# 8052.net
KiCad netlist of a schematic drawn in EAGLE
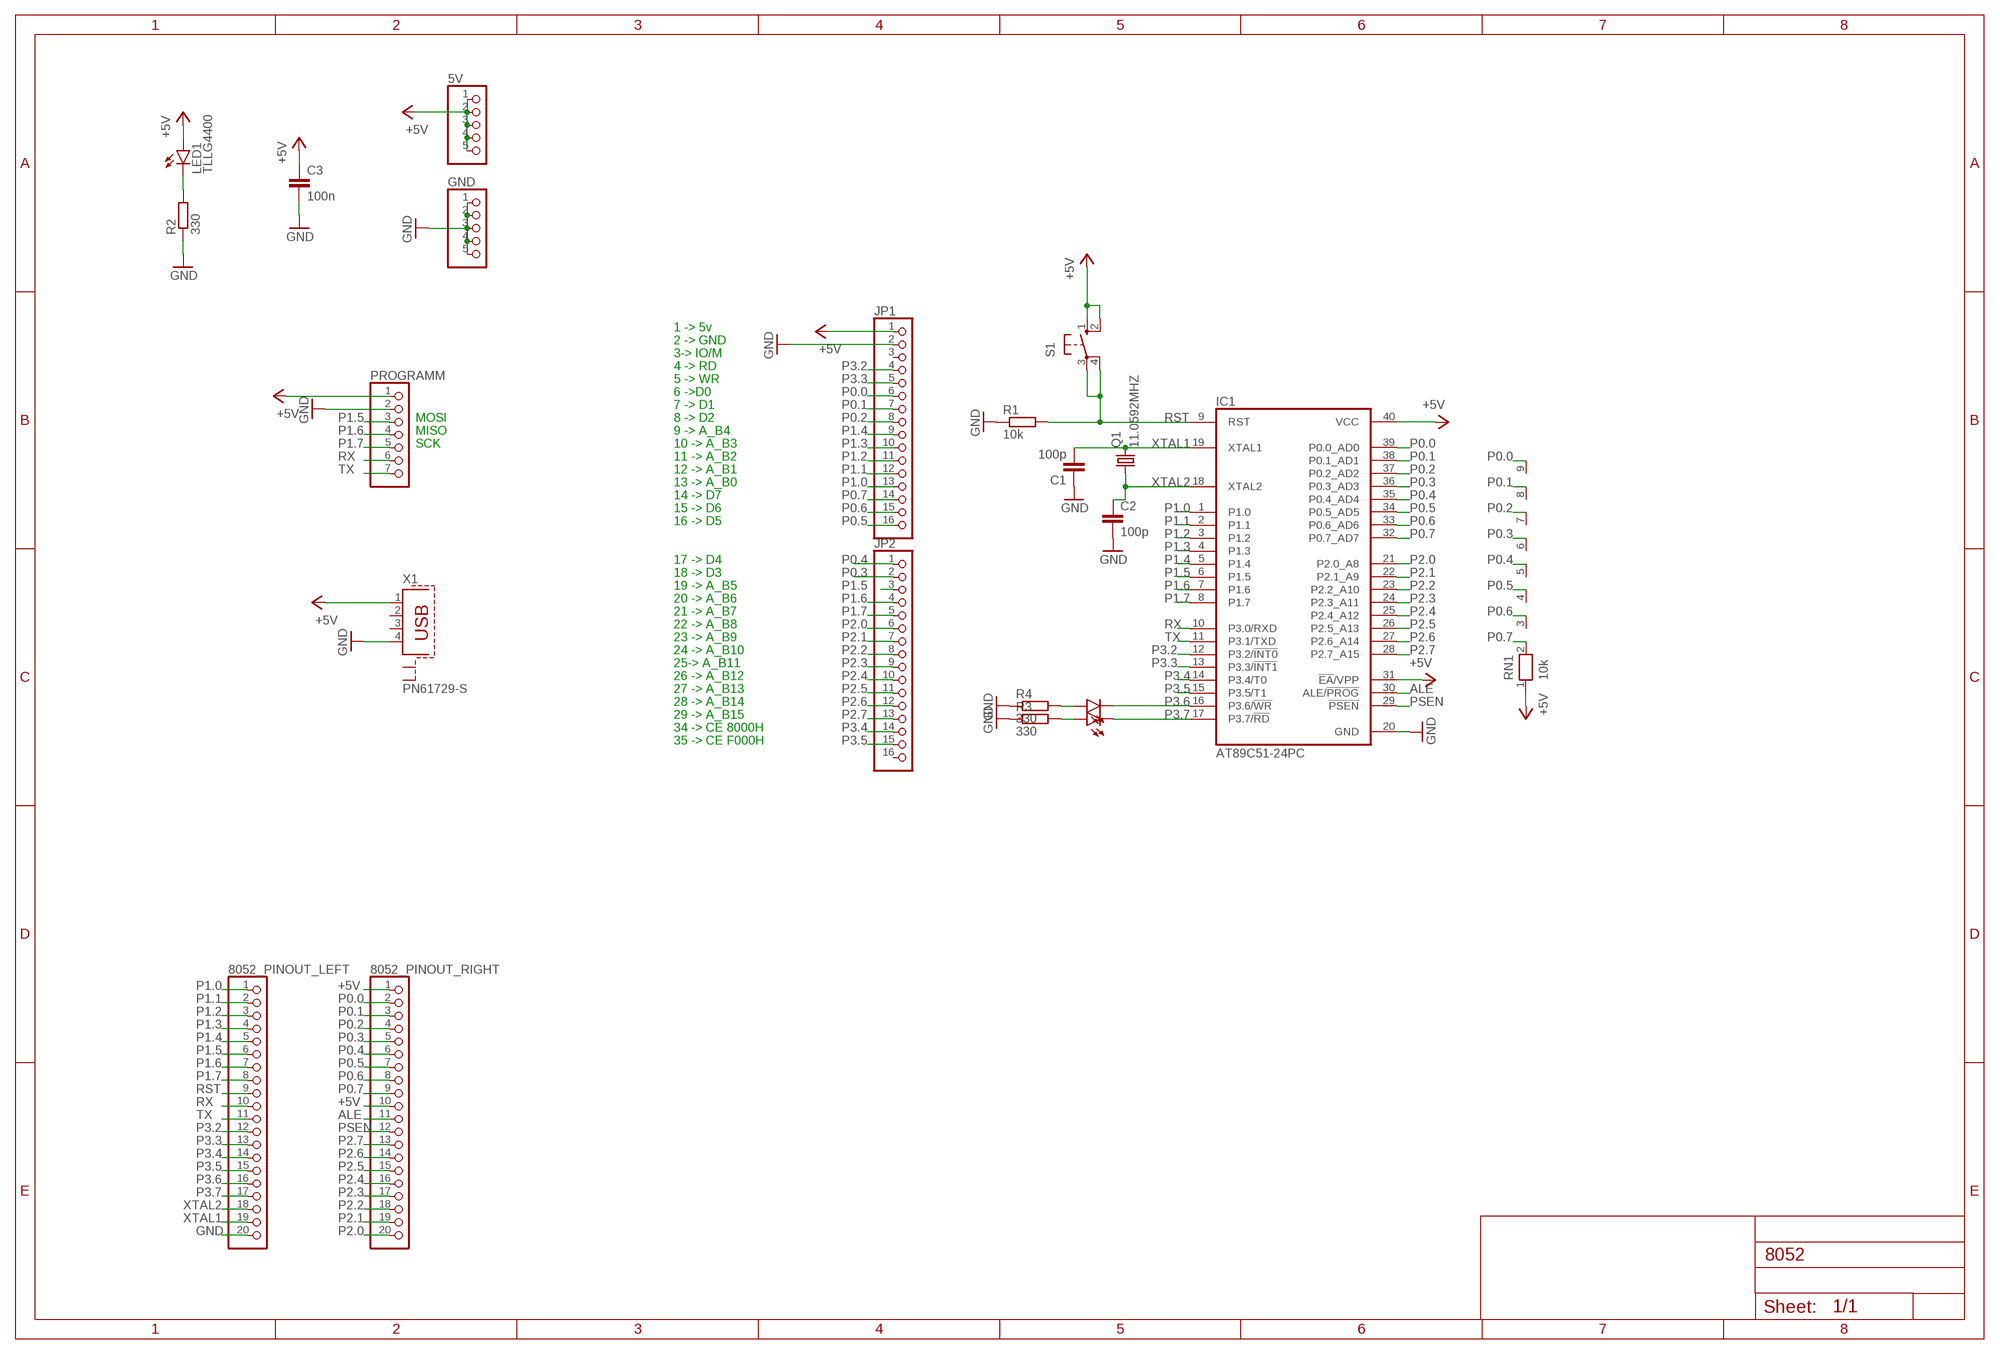
[diagram p0: schematic, sheet 1]

(export (version "E")
  (design (tool "Eeschema 10.0.6"))
  (components
    (comp (ref "5V")
      (value "PINHD-1X5")
      (footprint "eagle-import:1X05")
      (libsource (lib "eagle-import") (part "PINHD-1X5"))
    )
    (comp (ref "8052_PINOUT_LEFT")
      (value "PINHD-1X20")
      (footprint "eagle-import:1X20")
      (libsource (lib "eagle-import") (part "PINHD-1X20"))
    )
    (comp (ref "8052_PINOUT_RIGHT")
      (value "PINHD-1X20")
      (footprint "eagle-import:1X20")
      (libsource (lib "eagle-import") (part "PINHD-1X20"))
    )
    (comp (ref "C1")
      (value "100p")
      (footprint "eagle-import:C025-024X044")
      (libsource (lib "eagle-import") (part "C-EU025-024X044"))
    )
    (comp (ref "C2")
      (value "100p")
      (footprint "eagle-import:C025-024X044")
      (libsource (lib "eagle-import") (part "C-EU025-024X044"))
    )
    (comp (ref "C3")
      (value "100n")
      (footprint "eagle-import:C025-025X050")
      (libsource (lib "eagle-import") (part "C-EU025-025X050"))
    )
    (comp (ref "GND")
      (value "PINHD-1X5")
      (footprint "eagle-import:1X05")
      (libsource (lib "eagle-import") (part "PINHD-1X5"))
    )
    (comp (ref "IC1")
      (value "AT89C51-24PC")
      (footprint "eagle-import:DIL40")
      (libsource (lib "eagle-import") (part "AT89C51-PC24"))
    )
    (comp (ref "JP1")
      (value "PINHD-1X16")
      (footprint "eagle-import:1X16")
      (libsource (lib "eagle-import") (part "PINHD-1X16"))
    )
    (comp (ref "JP2")
      (value "PINHD-1X16")
      (footprint "eagle-import:1X16")
      (libsource (lib "eagle-import") (part "PINHD-1X16"))
    )
    (comp (ref "LED1")
      (value "TLLG4400")
      (footprint "eagle-import:LED3MM")
      (fields (field (name "MF") "VISHAY SEMICONDUCTOR"))
      (libsource (lib "eagle-import") (part "TLLG4400"))
    )
    (comp (ref "LED2")
      (value "TLLG4400")
      (footprint "eagle-import:LED3MM")
      (fields (field (name "MF") "VISHAY SEMICONDUCTOR"))
      (libsource (lib "eagle-import") (part "TLLG4400"))
    )
    (comp (ref "LED3")
      (value "TLLG4400")
      (footprint "eagle-import:LED3MM")
      (fields (field (name "MF") "VISHAY SEMICONDUCTOR"))
      (libsource (lib "eagle-import") (part "TLLG4400"))
    )
    (comp (ref "PROGRAMM")
      (value "PINHD-1X7/90")
      (footprint "eagle-import:1X07_90")
      (libsource (lib "eagle-import") (part "PINHD-1X7/90"))
    )
    (comp (ref "Q1")
      (value "11.0592MHZ")
      (footprint "eagle-import:HC49_S")
      (libsource (lib "eagle-import") (part "CRYSTALHC49S"))
    )
    (comp (ref "R1")
      (value "10k")
      (footprint "eagle-import:0207_7")
      (libsource (lib "eagle-import") (part "R-EU_0207/7"))
    )
    (comp (ref "R2")
      (value "330")
      (footprint "eagle-import:0207_7")
      (libsource (lib "eagle-import") (part "R-EU_0207/7"))
    )
    (comp (ref "R3")
      (value "330")
      (footprint "eagle-import:0207_7")
      (libsource (lib "eagle-import") (part "R-EU_0207/7"))
    )
    (comp (ref "R4")
      (value "330")
      (footprint "eagle-import:0207_7")
      (libsource (lib "eagle-import") (part "R-EU_0207/7"))
    )
    (comp (ref "RN1")
      (value "10k")
      (footprint "eagle-import:RN-9")
      (libsource (lib "eagle-import") (part "RN08"))
    )
    (comp (ref "S1")
      (value "10-XX")
      (footprint "eagle-import:B3F-10XX")
      (fields (field (name "MPN") "B3F-1000"))
      (libsource (lib "eagle-import") (part "10-XX"))
    )
    (comp (ref "X1")
      (value "PN61729-S")
      (footprint "eagle-import:PN61729-S")
      (libsource (lib "eagle-import") (part "PN61729-S"))
    )
  )
  (nets
    (net (code "1") (name "+5V") (class "Default")
      (node (ref "5V") (pin "1") (pinfunction "1_1") (pintype "passive"))
      (node (ref "5V") (pin "2") (pinfunction "2_2") (pintype "passive"))
      (node (ref "5V") (pin "3") (pinfunction "3_3") (pintype "passive"))
      (node (ref "5V") (pin "4") (pinfunction "4_4") (pintype "passive"))
      (node (ref "5V") (pin "5") (pinfunction "5_5") (pintype "passive"))
      (node (ref "8052_PINOUT_RIGHT") (pin "1") (pinfunction "1_1") (pintype "passive"))
      (node (ref "8052_PINOUT_RIGHT") (pin "10") (pinfunction "10_10") (pintype "passive"))
      (node (ref "C3") (pin "1") (pinfunction "1_1") (pintype "passive"))
      (node (ref "IC1") (pin "31") (pinfunction "~{EA}/VPP_31") (pintype "input"))
      (node (ref "IC1") (pin "40") (pinfunction "VCC_40") (pintype "power_in"))
      (node (ref "JP1") (pin "1") (pinfunction "1_1") (pintype "passive"))
      (node (ref "LED1") (pin "A") (pinfunction "A_A") (pintype "passive"))
      (node (ref "PROGRAMM") (pin "1") (pinfunction "1_1") (pintype "passive"))
      (node (ref "RN1") (pin "1") (pinfunction "1_1") (pintype "passive"))
      (node (ref "S1") (pin "1") (pinfunction "S_1") (pintype "passive"))
      (node (ref "S1") (pin "2") (pinfunction "S1_2") (pintype "passive"))
      (node (ref "X1") (pin "1") (pinfunction "1_1") (pintype "passive"))
    )
    (net (code "2") (name "/ALE") (class "Default")
      (node (ref "8052_PINOUT_RIGHT") (pin "11") (pinfunction "11_11") (pintype "passive"))
      (node (ref "IC1") (pin "30") (pinfunction "ALE/~{PROG}_30") (pintype "output"))
    )
    (net (code "3") (name "/P0.0") (class "Default")
      (node (ref "8052_PINOUT_RIGHT") (pin "2") (pinfunction "2_2") (pintype "passive"))
      (node (ref "IC1") (pin "39") (pinfunction "P0.0_AD0_39") (pintype "bidirectional"))
      (node (ref "JP1") (pin "6") (pinfunction "6_6") (pintype "passive"))
      (node (ref "RN1") (pin "9") (pinfunction "9_9") (pintype "passive"))
    )
    (net (code "4") (name "/P0.1") (class "Default")
      (node (ref "8052_PINOUT_RIGHT") (pin "3") (pinfunction "3_3") (pintype "passive"))
      (node (ref "IC1") (pin "38") (pinfunction "P0.1_AD1_38") (pintype "bidirectional"))
      (node (ref "JP1") (pin "7") (pinfunction "7_7") (pintype "passive"))
      (node (ref "RN1") (pin "8") (pinfunction "8_8") (pintype "passive"))
    )
    (net (code "5") (name "/P0.2") (class "Default")
      (node (ref "8052_PINOUT_RIGHT") (pin "4") (pinfunction "4_4") (pintype "passive"))
      (node (ref "IC1") (pin "37") (pinfunction "P0.2_AD2_37") (pintype "bidirectional"))
      (node (ref "JP1") (pin "8") (pinfunction "8_8") (pintype "passive"))
      (node (ref "RN1") (pin "7") (pinfunction "7_7") (pintype "passive"))
    )
    (net (code "6") (name "/P0.3") (class "Default")
      (node (ref "8052_PINOUT_RIGHT") (pin "5") (pinfunction "5_5") (pintype "passive"))
      (node (ref "IC1") (pin "36") (pinfunction "P0.3_AD3_36") (pintype "bidirectional"))
      (node (ref "JP2") (pin "2") (pinfunction "2_2") (pintype "passive"))
      (node (ref "RN1") (pin "6") (pinfunction "6_6") (pintype "passive"))
    )
    (net (code "7") (name "/P0.4") (class "Default")
      (node (ref "8052_PINOUT_RIGHT") (pin "6") (pinfunction "6_6") (pintype "passive"))
      (node (ref "IC1") (pin "35") (pinfunction "P0.4_AD4_35") (pintype "bidirectional"))
      (node (ref "JP2") (pin "1") (pinfunction "1_1") (pintype "passive"))
      (node (ref "RN1") (pin "5") (pinfunction "5_5") (pintype "passive"))
    )
    (net (code "8") (name "/P0.5") (class "Default")
      (node (ref "8052_PINOUT_RIGHT") (pin "7") (pinfunction "7_7") (pintype "passive"))
      (node (ref "IC1") (pin "34") (pinfunction "P0.5_AD5_34") (pintype "bidirectional"))
      (node (ref "JP1") (pin "16") (pinfunction "16_16") (pintype "passive"))
      (node (ref "RN1") (pin "4") (pinfunction "4_4") (pintype "passive"))
    )
    (net (code "9") (name "/P0.6") (class "Default")
      (node (ref "8052_PINOUT_RIGHT") (pin "8") (pinfunction "8_8") (pintype "passive"))
      (node (ref "IC1") (pin "33") (pinfunction "P0.6_AD6_33") (pintype "bidirectional"))
      (node (ref "JP1") (pin "15") (pinfunction "15_15") (pintype "passive"))
      (node (ref "RN1") (pin "3") (pinfunction "3_3") (pintype "passive"))
    )
    (net (code "10") (name "/P0.7") (class "Default")
      (node (ref "8052_PINOUT_RIGHT") (pin "9") (pinfunction "9_9") (pintype "passive"))
      (node (ref "IC1") (pin "32") (pinfunction "P0.7_AD7_32") (pintype "bidirectional"))
      (node (ref "JP1") (pin "14") (pinfunction "14_14") (pintype "passive"))
      (node (ref "RN1") (pin "2") (pinfunction "2_2") (pintype "passive"))
    )
    (net (code "11") (name "/P1.0") (class "Default")
      (node (ref "8052_PINOUT_LEFT") (pin "1") (pinfunction "1_1") (pintype "passive"))
      (node (ref "IC1") (pin "1") (pinfunction "P1.0_1") (pintype "bidirectional"))
      (node (ref "JP1") (pin "13") (pinfunction "13_13") (pintype "passive"))
    )
    (net (code "12") (name "/P1.1") (class "Default")
      (node (ref "8052_PINOUT_LEFT") (pin "2") (pinfunction "2_2") (pintype "passive"))
      (node (ref "IC1") (pin "2") (pinfunction "P1.1_2") (pintype "bidirectional"))
      (node (ref "JP1") (pin "12") (pinfunction "12_12") (pintype "passive"))
    )
    (net (code "13") (name "/P1.2") (class "Default")
      (node (ref "8052_PINOUT_LEFT") (pin "3") (pinfunction "3_3") (pintype "passive"))
      (node (ref "IC1") (pin "3") (pinfunction "P1.2_3") (pintype "bidirectional"))
      (node (ref "JP1") (pin "11") (pinfunction "11_11") (pintype "passive"))
    )
    (net (code "14") (name "/P1.3") (class "Default")
      (node (ref "8052_PINOUT_LEFT") (pin "4") (pinfunction "4_4") (pintype "passive"))
      (node (ref "IC1") (pin "4") (pinfunction "P1.3_4") (pintype "bidirectional"))
      (node (ref "JP1") (pin "10") (pinfunction "10_10") (pintype "passive"))
    )
    (net (code "15") (name "/P1.4") (class "Default")
      (node (ref "8052_PINOUT_LEFT") (pin "5") (pinfunction "5_5") (pintype "passive"))
      (node (ref "IC1") (pin "5") (pinfunction "P1.4_5") (pintype "bidirectional"))
      (node (ref "JP1") (pin "9") (pinfunction "9_9") (pintype "passive"))
    )
    (net (code "16") (name "/P1.5") (class "Default")
      (node (ref "8052_PINOUT_LEFT") (pin "6") (pinfunction "6_6") (pintype "passive"))
      (node (ref "IC1") (pin "6") (pinfunction "P1.5_6") (pintype "bidirectional"))
      (node (ref "JP2") (pin "3") (pinfunction "3_3") (pintype "passive"))
      (node (ref "PROGRAMM") (pin "3") (pinfunction "3_3") (pintype "passive"))
    )
    (net (code "17") (name "/P1.6") (class "Default")
      (node (ref "8052_PINOUT_LEFT") (pin "7") (pinfunction "7_7") (pintype "passive"))
      (node (ref "IC1") (pin "7") (pinfunction "P1.6_7") (pintype "bidirectional"))
      (node (ref "JP2") (pin "4") (pinfunction "4_4") (pintype "passive"))
      (node (ref "PROGRAMM") (pin "4") (pinfunction "4_4") (pintype "passive"))
    )
    (net (code "18") (name "/P1.7") (class "Default")
      (node (ref "8052_PINOUT_LEFT") (pin "8") (pinfunction "8_8") (pintype "passive"))
      (node (ref "IC1") (pin "8") (pinfunction "P1.7_8") (pintype "bidirectional"))
      (node (ref "JP2") (pin "5") (pinfunction "5_5") (pintype "passive"))
      (node (ref "PROGRAMM") (pin "5") (pinfunction "5_5") (pintype "passive"))
    )
    (net (code "19") (name "/P2.0") (class "Default")
      (node (ref "8052_PINOUT_RIGHT") (pin "20") (pinfunction "20_20") (pintype "passive"))
      (node (ref "IC1") (pin "21") (pinfunction "P2.0_A8_21") (pintype "bidirectional"))
      (node (ref "JP2") (pin "6") (pinfunction "6_6") (pintype "passive"))
    )
    (net (code "20") (name "/P2.1") (class "Default")
      (node (ref "8052_PINOUT_RIGHT") (pin "19") (pinfunction "19_19") (pintype "passive"))
      (node (ref "IC1") (pin "22") (pinfunction "P2.1_A9_22") (pintype "bidirectional"))
      (node (ref "JP2") (pin "7") (pinfunction "7_7") (pintype "passive"))
    )
    (net (code "21") (name "/P2.2") (class "Default")
      (node (ref "8052_PINOUT_RIGHT") (pin "18") (pinfunction "18_18") (pintype "passive"))
      (node (ref "IC1") (pin "23") (pinfunction "P2.2_A10_23") (pintype "bidirectional"))
      (node (ref "JP2") (pin "8") (pinfunction "8_8") (pintype "passive"))
    )
    (net (code "22") (name "/P2.3") (class "Default")
      (node (ref "8052_PINOUT_RIGHT") (pin "17") (pinfunction "17_17") (pintype "passive"))
      (node (ref "IC1") (pin "24") (pinfunction "P2.3_A11_24") (pintype "bidirectional"))
      (node (ref "JP2") (pin "9") (pinfunction "9_9") (pintype "passive"))
    )
    (net (code "23") (name "/P2.4") (class "Default")
      (node (ref "8052_PINOUT_RIGHT") (pin "16") (pinfunction "16_16") (pintype "passive"))
      (node (ref "IC1") (pin "25") (pinfunction "P2.4_A12_25") (pintype "bidirectional"))
      (node (ref "JP2") (pin "10") (pinfunction "10_10") (pintype "passive"))
    )
    (net (code "24") (name "/P2.5") (class "Default")
      (node (ref "8052_PINOUT_RIGHT") (pin "15") (pinfunction "15_15") (pintype "passive"))
      (node (ref "IC1") (pin "26") (pinfunction "P2.5_A13_26") (pintype "bidirectional"))
      (node (ref "JP2") (pin "11") (pinfunction "11_11") (pintype "passive"))
    )
    (net (code "25") (name "/P2.6") (class "Default")
      (node (ref "8052_PINOUT_RIGHT") (pin "14") (pinfunction "14_14") (pintype "passive"))
      (node (ref "IC1") (pin "27") (pinfunction "P2.6_A14_27") (pintype "bidirectional"))
      (node (ref "JP2") (pin "12") (pinfunction "12_12") (pintype "passive"))
    )
    (net (code "26") (name "/P2.7") (class "Default")
      (node (ref "8052_PINOUT_RIGHT") (pin "13") (pinfunction "13_13") (pintype "passive"))
      (node (ref "IC1") (pin "28") (pinfunction "P2.7_A15_28") (pintype "bidirectional"))
      (node (ref "JP2") (pin "13") (pinfunction "13_13") (pintype "passive"))
    )
    (net (code "27") (name "/P3.2") (class "Default")
      (node (ref "8052_PINOUT_LEFT") (pin "12") (pinfunction "12_12") (pintype "passive"))
      (node (ref "IC1") (pin "12") (pinfunction "P3.2/~{INT0}_12") (pintype "bidirectional"))
      (node (ref "JP1") (pin "4") (pinfunction "4_4") (pintype "passive"))
    )
    (net (code "28") (name "/P3.3") (class "Default")
      (node (ref "8052_PINOUT_LEFT") (pin "13") (pinfunction "13_13") (pintype "passive"))
      (node (ref "IC1") (pin "13") (pinfunction "P3.3/~{INT1}_13") (pintype "bidirectional"))
      (node (ref "JP1") (pin "5") (pinfunction "5_5") (pintype "passive"))
    )
    (net (code "29") (name "/P3.4") (class "Default")
      (node (ref "8052_PINOUT_LEFT") (pin "14") (pinfunction "14_14") (pintype "passive"))
      (node (ref "IC1") (pin "14") (pinfunction "P3.4/T0_14") (pintype "bidirectional"))
      (node (ref "JP2") (pin "14") (pinfunction "14_14") (pintype "passive"))
    )
    (net (code "30") (name "/P3.5") (class "Default")
      (node (ref "8052_PINOUT_LEFT") (pin "15") (pinfunction "15_15") (pintype "passive"))
      (node (ref "IC1") (pin "15") (pinfunction "P3.5/T1_15") (pintype "bidirectional"))
      (node (ref "JP2") (pin "15") (pinfunction "15_15") (pintype "passive"))
    )
    (net (code "31") (name "/P3.6") (class "Default")
      (node (ref "8052_PINOUT_LEFT") (pin "16") (pinfunction "16_16") (pintype "passive"))
      (node (ref "IC1") (pin "16") (pinfunction "P3.6/~{WR}_16") (pintype "bidirectional"))
      (node (ref "LED2") (pin "K") (pinfunction "C_K") (pintype "passive"))
    )
    (net (code "32") (name "/P3.7") (class "Default")
      (node (ref "8052_PINOUT_LEFT") (pin "17") (pinfunction "17_17") (pintype "passive"))
      (node (ref "IC1") (pin "17") (pinfunction "P3.7/~{RD}_17") (pintype "bidirectional"))
      (node (ref "LED3") (pin "K") (pinfunction "C_K") (pintype "passive"))
    )
    (net (code "33") (name "/PSEN") (class "Default")
      (node (ref "8052_PINOUT_RIGHT") (pin "12") (pinfunction "12_12") (pintype "passive"))
      (node (ref "IC1") (pin "29") (pinfunction "~{PSEN}_29") (pintype "output"))
    )
    (net (code "34") (name "/RST") (class "Default")
      (node (ref "8052_PINOUT_LEFT") (pin "9") (pinfunction "9_9") (pintype "passive"))
      (node (ref "IC1") (pin "9") (pinfunction "RST_9") (pintype "input"))
      (node (ref "R1") (pin "2") (pinfunction "2_2") (pintype "passive"))
      (node (ref "S1") (pin "3") (pinfunction "P_3") (pintype "passive"))
      (node (ref "S1") (pin "4") (pinfunction "P1_4") (pintype "passive"))
    )
    (net (code "35") (name "/RX") (class "Default")
      (node (ref "8052_PINOUT_LEFT") (pin "10") (pinfunction "10_10") (pintype "passive"))
      (node (ref "IC1") (pin "10") (pinfunction "P3.0/RXD_10") (pintype "bidirectional"))
      (node (ref "PROGRAMM") (pin "6") (pinfunction "6_6") (pintype "passive"))
    )
    (net (code "36") (name "/TX") (class "Default")
      (node (ref "8052_PINOUT_LEFT") (pin "11") (pinfunction "11_11") (pintype "passive"))
      (node (ref "IC1") (pin "11") (pinfunction "P3.1/TXD_11") (pintype "bidirectional"))
      (node (ref "PROGRAMM") (pin "7") (pinfunction "7_7") (pintype "passive"))
    )
    (net (code "37") (name "/XTAL1") (class "Default")
      (node (ref "8052_PINOUT_LEFT") (pin "19") (pinfunction "19_19") (pintype "passive"))
      (node (ref "C1") (pin "2") (pinfunction "2_2") (pintype "passive"))
      (node (ref "IC1") (pin "19") (pinfunction "XTAL1_19") (pintype "input"))
      (node (ref "Q1") (pin "2") (pinfunction "2_2") (pintype "passive"))
    )
    (net (code "38") (name "/XTAL2") (class "Default")
      (node (ref "8052_PINOUT_LEFT") (pin "18") (pinfunction "18_18") (pintype "passive"))
      (node (ref "C2") (pin "1") (pinfunction "1_1") (pintype "passive"))
      (node (ref "IC1") (pin "18") (pinfunction "XTAL2_18") (pintype "input"))
      (node (ref "Q1") (pin "1") (pinfunction "1_1") (pintype "passive"))
    )
    (net (code "39") (name "GND") (class "Default")
      (node (ref "8052_PINOUT_LEFT") (pin "20") (pinfunction "20_20") (pintype "passive"))
      (node (ref "C1") (pin "1") (pinfunction "1_1") (pintype "passive"))
      (node (ref "C2") (pin "2") (pinfunction "2_2") (pintype "passive"))
      (node (ref "C3") (pin "2") (pinfunction "2_2") (pintype "passive"))
      (node (ref "GND") (pin "1") (pinfunction "1_1") (pintype "passive"))
      (node (ref "GND") (pin "2") (pinfunction "2_2") (pintype "passive"))
      (node (ref "GND") (pin "3") (pinfunction "3_3") (pintype "passive"))
      (node (ref "GND") (pin "4") (pinfunction "4_4") (pintype "passive"))
      (node (ref "GND") (pin "5") (pinfunction "5_5") (pintype "passive"))
      (node (ref "IC1") (pin "20") (pinfunction "GND_20") (pintype "power_in"))
      (node (ref "JP1") (pin "2") (pinfunction "2_2") (pintype "passive"))
      (node (ref "PROGRAMM") (pin "2") (pinfunction "2_2") (pintype "passive"))
      (node (ref "R1") (pin "1") (pinfunction "1_1") (pintype "passive"))
      (node (ref "R2") (pin "1") (pinfunction "1_1") (pintype "passive"))
      (node (ref "R3") (pin "1") (pinfunction "1_1") (pintype "passive"))
      (node (ref "R4") (pin "1") (pinfunction "1_1") (pintype "passive"))
      (node (ref "X1") (pin "4") (pinfunction "4_4") (pintype "passive"))
    )
    (net (code "40") (name "Net-(LED1-C)") (class "Default")
      (node (ref "LED1") (pin "K") (pinfunction "C_K") (pintype "passive"))
      (node (ref "R2") (pin "2") (pinfunction "2_2") (pintype "passive"))
    )
    (net (code "41") (name "Net-(LED2-PadA)") (class "Default")
      (node (ref "LED2") (pin "A") (pinfunction "A_A") (pintype "passive"))
      (node (ref "R4") (pin "2") (pinfunction "2_2") (pintype "passive"))
    )
    (net (code "42") (name "Net-(LED3-PadA)") (class "Default")
      (node (ref "LED3") (pin "A") (pinfunction "A_A") (pintype "passive"))
      (node (ref "R3") (pin "2") (pinfunction "2_2") (pintype "passive"))
    )
    (net (code "43") (name "unconnected-(JP1-Pad3)") (class "Default")
      (node (ref "JP1") (pin "3") (pinfunction "3_3") (pintype "passive"))
    )
    (net (code "44") (name "unconnected-(JP2-Pad16)") (class "Default")
      (node (ref "JP2") (pin "16") (pinfunction "16_16") (pintype "passive"))
    )
    (net (code "45") (name "unconnected-(X1-Pad2)") (class "Default")
      (node (ref "X1") (pin "2") (pinfunction "2_2") (pintype "passive"))
    )
    (net (code "46") (name "unconnected-(X1-Pad3)") (class "Default")
      (node (ref "X1") (pin "3") (pinfunction "3_3") (pintype "passive"))
    )
    (net (code "47") (name "unconnected-(X1-PadS1)") (class "Default")
      (node (ref "X1") (pin "S1") (pinfunction "S1_S1") (pintype "passive"))
    )
    (net (code "48") (name "unconnected-(X1-PadS2)") (class "Default")
      (node (ref "X1") (pin "S2") (pinfunction "S2_S2") (pintype "passive"))
    )
  )
)
